# CurrentSense.net
KiCad netlist of a schematic drawn in Altium Designer
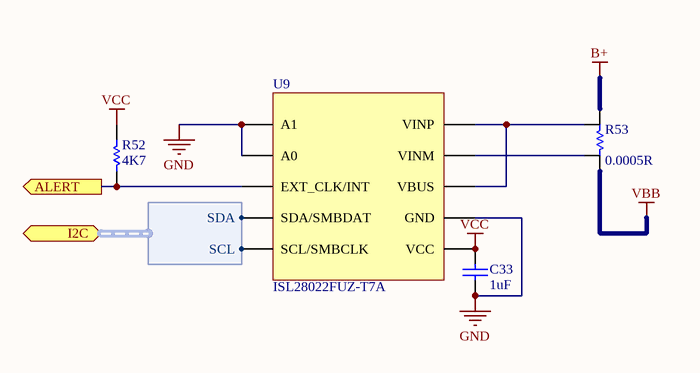
[diagram p0: CurrentSense.SchDoc]

(export (version "E")
  (design (tool "Eeschema 10.0.6"))
  (components
    (comp (ref "C33")
      (value "1uF")
      (footprint "C0402[1005X55]")
      (description "1uF 6.3V 10% 0402 (1005 Metric)")
      (fields (field (name "TOLERANCE") "10%") (field (name "PARTNUMBER") "GRM155R70J105KA12D"))
      (libsource (lib "Capacitors") (part "CAP_1uF_6.3V_0402_10%"))
    )
    (comp (ref "R52")
      (value "4K7")
      (footprint "R0402[1005]")
      (description "4K7 0.063W 1% 0402 (1005 Metric)")
      (fields (field (name "MANUFACTURER") "KOA Speer") (field (name "PARTNUMBER") "RK73H1ETTP4701F"))
      (libsource (lib "Resistors") (part "RES_4K7_0402_1%"))
    )
    (comp (ref "R53")
      (value "0.0005R")
      (footprint "WSL2726")
      (description "Current Sense Resistor, 0.0005R")
      (fields (field (name "PARTNUMBER") "WSLP2726L5000FEA") (field (name "MANUFACTURER") "Vishay / Dale"))
      (libsource (lib "Components") (part "WSLP2726"))
    )
    (comp (ref "U9")
      (value "ISL28022FUZ-T7A")
      (footprint "MSOP-10")
      (fields (field (name "MANUFACTURER") "Intersil"))
      (libsource (lib "ICs") (part "ISL28022FUZ-T7A"))
    )
  )
  (nets
    (net (code "2") (name "/ALERT") (class "Default")
      (node (ref "R52") (pin "1") (pinfunction "1_1") (pintype "passive"))
      (node (ref "U9") (pin "3") (pinfunction "EXT_CLK/INT_3") (pintype "passive"))
    )
    (net (code "3") (name "/SCL") (class "Default")
      (node (ref "U9") (pin "5") (pinfunction "SCL/SMBCLK_5") (pintype "passive"))
    )
    (net (code "4") (name "/SDA") (class "Default")
      (node (ref "U9") (pin "4") (pinfunction "SDA/SMBDAT_4") (pintype "passive"))
    )
    (net (code "6") (name "B+") (class "Default")
      (node (ref "R53") (pin "2") (pinfunction "2_2") (pintype "passive"))
    )
    (net (code "7") (name "GND") (class "Default")
      (node (ref "C33") (pin "1") (pinfunction "1_1") (pintype "passive"))
      (node (ref "U9") (pin "1") (pinfunction "A1_1") (pintype "passive"))
      (node (ref "U9") (pin "2") (pinfunction "A0_2") (pintype "passive"))
      (node (ref "U9") (pin "7") (pinfunction "GND_7") (pintype "power_in"))
    )
    (net (code "8") (name "Net-(U9-VBUS)") (class "Default")
      (node (ref "R53") (pin "4") (pinfunction "4_4") (pintype "passive"))
      (node (ref "U9") (pin "10") (pinfunction "VINP_10") (pintype "passive"))
      (node (ref "U9") (pin "8") (pinfunction "VBUS_8") (pintype "passive"))
    )
    (net (code "9") (name "Net-(U9-VINM)") (class "Default")
      (node (ref "R53") (pin "3") (pinfunction "3_3") (pintype "passive"))
      (node (ref "U9") (pin "9") (pinfunction "VINM_9") (pintype "passive"))
    )
    (net (code "10") (name "VBB") (class "Default")
      (node (ref "R53") (pin "1") (pinfunction "1_1") (pintype "passive"))
    )
    (net (code "11") (name "VCC") (class "Default")
      (node (ref "C33") (pin "2") (pinfunction "2_2") (pintype "passive"))
      (node (ref "R52") (pin "2") (pinfunction "2_2") (pintype "passive"))
      (node (ref "U9") (pin "6") (pinfunction "VCC_6") (pintype "power_in"))
    )
  )
)
